# vulcan1.net
KiCad netlist of a schematic drawn in EAGLE
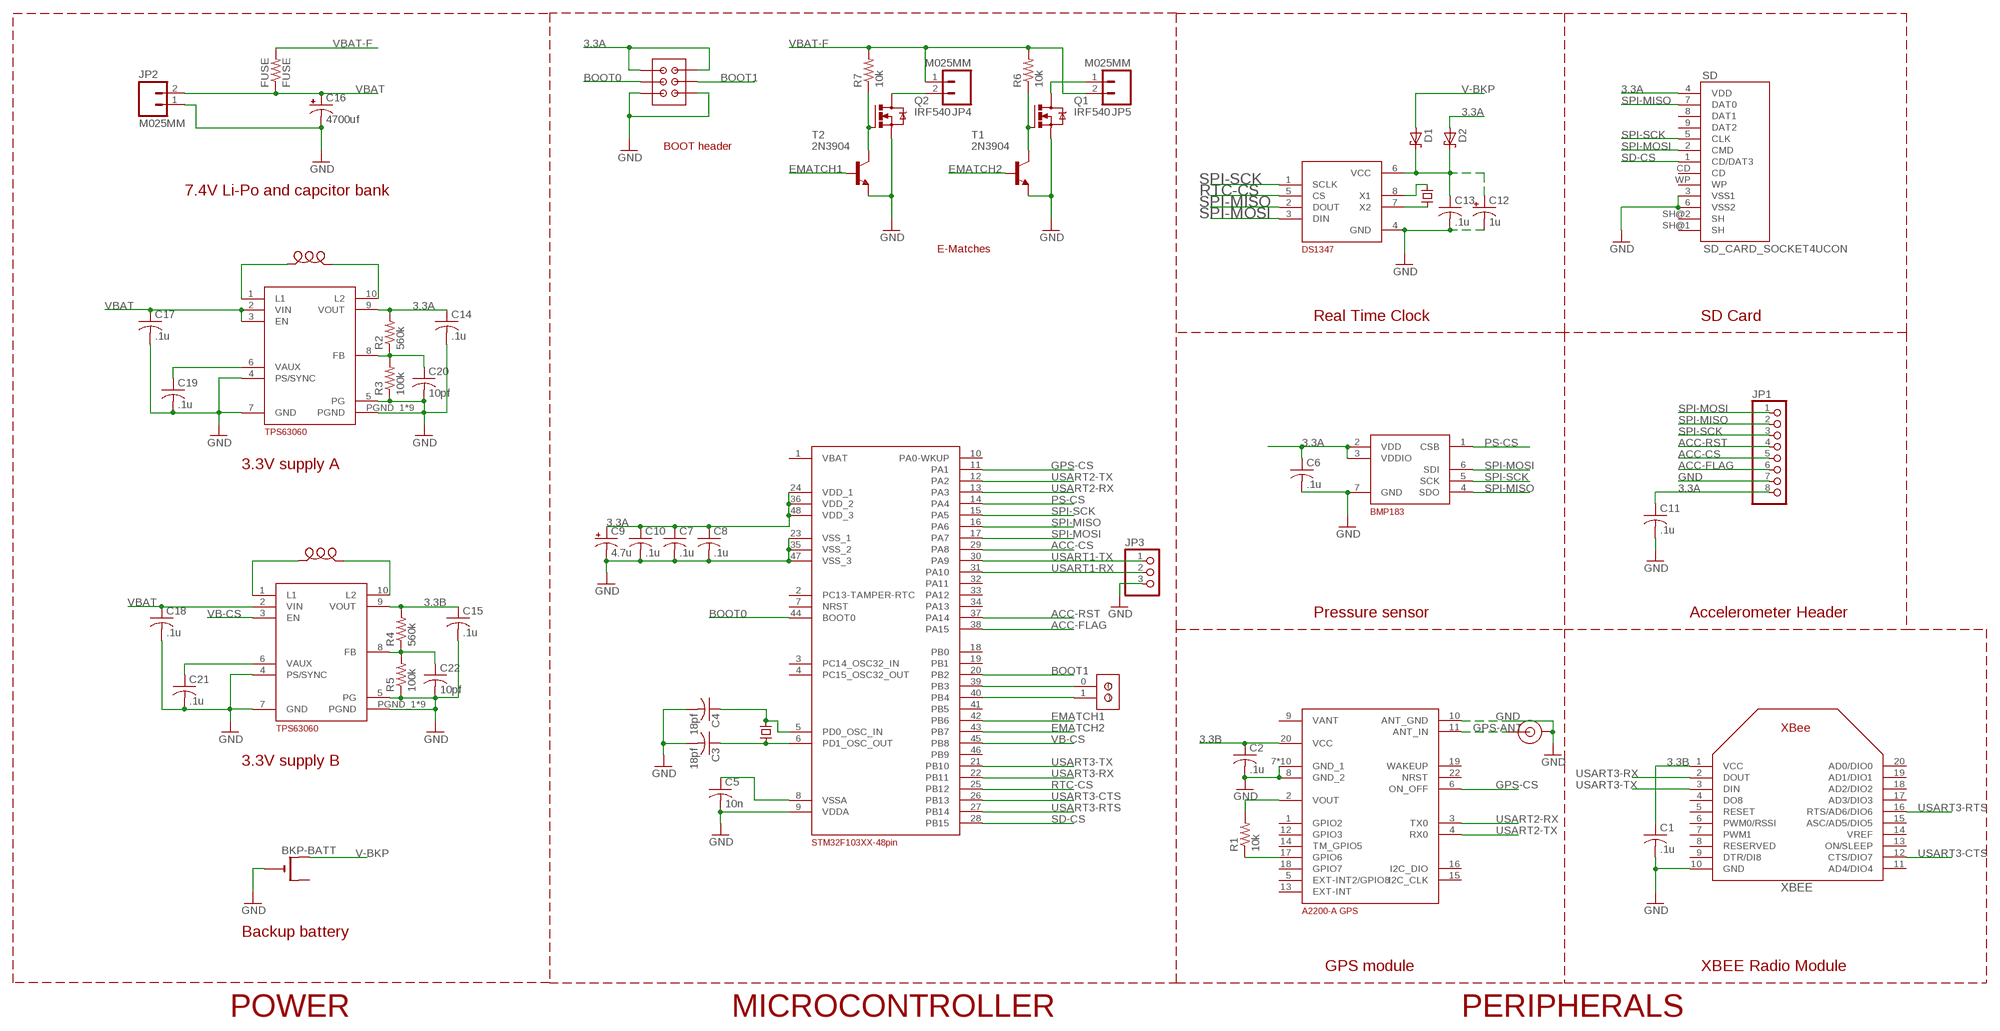
[diagram p0: schematic, sheet 1]

(export (version "E")
  (design (tool "Eeschema 10.0.6"))
  (components
    (comp (ref "A2200-A")
      (value "A2200-A")
      (footprint "eagle-import:GPS-MODULE")
      (libsource (lib "eagle-import") (part "A2200-A"))
    )
    (comp (ref "BKP-BATT")
      (value "CR1220THM")
      (footprint "eagle-import:CR1220-THM")
      (libsource (lib "eagle-import") (part "CR1220THM"))
    )
    (comp (ref "BMP1")
      (value "BMP183")
      (footprint "eagle-import:LGA-7")
      (libsource (lib "eagle-import") (part "BMP183"))
    )
    (comp (ref "C1")
      (value ".1u")
      (footprint "eagle-import:C025-030X050")
      (libsource (lib "eagle-import") (part "C-US025-030X050"))
    )
    (comp (ref "C2")
      (value ".1u")
      (footprint "eagle-import:C025-030X050")
      (libsource (lib "eagle-import") (part "C-US025-030X050"))
    )
    (comp (ref "C3")
      (value "18pf")
      (footprint "eagle-import:C025-030X050")
      (libsource (lib "eagle-import") (part "C-US025-030X050"))
    )
    (comp (ref "C4")
      (value "18pf")
      (footprint "eagle-import:C025-030X050")
      (libsource (lib "eagle-import") (part "C-US025-030X050"))
    )
    (comp (ref "C5")
      (value "10n")
      (footprint "eagle-import:C025-030X050")
      (libsource (lib "eagle-import") (part "C-US025-030X050"))
    )
    (comp (ref "C6")
      (value ".1u")
      (footprint "eagle-import:C025-030X050")
      (libsource (lib "eagle-import") (part "C-US025-030X050"))
    )
    (comp (ref "C7")
      (value ".1u")
      (footprint "eagle-import:C025-030X050")
      (libsource (lib "eagle-import") (part "C-US025-030X050"))
    )
    (comp (ref "C8")
      (value ".1u")
      (footprint "eagle-import:C025-030X050")
      (libsource (lib "eagle-import") (part "C-US025-030X050"))
    )
    (comp (ref "C9")
      (value "4.7u")
      (footprint "eagle-import:E2,5-6E")
      (libsource (lib "eagle-import") (part "CPOL-USE2,5-6E"))
    )
    (comp (ref "C10")
      (value ".1u")
      (footprint "eagle-import:C025-030X050")
      (libsource (lib "eagle-import") (part "C-US025-030X050"))
    )
    (comp (ref "C11")
      (value ".1u")
      (footprint "eagle-import:C025-030X050")
      (libsource (lib "eagle-import") (part "C-US025-030X050"))
    )
    (comp (ref "C12")
      (value "1u")
      (footprint "eagle-import:E2,5-6E")
      (libsource (lib "eagle-import") (part "CPOL-USE2,5-6E"))
    )
    (comp (ref "C13")
      (value ".1u")
      (footprint "eagle-import:C025-030X050")
      (libsource (lib "eagle-import") (part "C-US025-030X050"))
    )
    (comp (ref "C14")
      (value ".1u")
      (footprint "eagle-import:C025-030X050")
      (libsource (lib "eagle-import") (part "C-US025-030X050"))
    )
    (comp (ref "C15")
      (value ".1u")
      (footprint "eagle-import:C025-030X050")
      (libsource (lib "eagle-import") (part "C-US025-030X050"))
    )
    (comp (ref "C16")
      (value "4700uf")
      (footprint "eagle-import:E5-13")
      (libsource (lib "eagle-import") (part "CPOL-USE5-13"))
    )
    (comp (ref "C17")
      (value ".1u")
      (footprint "eagle-import:C025-030X050")
      (libsource (lib "eagle-import") (part "C-US025-030X050"))
    )
    (comp (ref "C18")
      (value ".1u")
      (footprint "eagle-import:C025-030X050")
      (libsource (lib "eagle-import") (part "C-US025-030X050"))
    )
    (comp (ref "C19")
      (value ".1u")
      (footprint "eagle-import:C025-030X050")
      (libsource (lib "eagle-import") (part "C-US025-030X050"))
    )
    (comp (ref "C20")
      (value "10pf")
      (footprint "eagle-import:C025-030X050")
      (libsource (lib "eagle-import") (part "C-US025-030X050"))
    )
    (comp (ref "C21")
      (value ".1u")
      (footprint "eagle-import:C025-030X050")
      (libsource (lib "eagle-import") (part "C-US025-030X050"))
    )
    (comp (ref "C22")
      (value "10pf")
      (footprint "eagle-import:C025-030X050")
      (libsource (lib "eagle-import") (part "C-US025-030X050"))
    )
    (comp (ref "D1")
      (value "SCHOTTKY-DIODEDO35-7")
      (footprint "eagle-import:DO35-7")
      (libsource (lib "eagle-import") (part "SCHOTTKY-DIODEDO35-7"))
    )
    (comp (ref "D2")
      (value "SCHOTTKY-DIODEDO35-7")
      (footprint "eagle-import:DO35-7")
      (libsource (lib "eagle-import") (part "SCHOTTKY-DIODEDO35-7"))
    )
    (comp (ref "DS1")
      (value "DS1347")
      (footprint "eagle-import:TDFN-T822-2")
      (libsource (lib "eagle-import") (part "DS1347"))
    )
    (comp (ref "FUSE")
      (value "FUSE")
      (footprint "eagle-import:0204_7")
      (libsource (lib "eagle-import") (part "R-US_0204/7"))
    )
    (comp (ref "JP1")
      (value "PINHD-1X8CLEANBIG")
      (footprint "eagle-import:1X08-CLEANBIG")
      (libsource (lib "eagle-import") (part "PINHD-1X8CLEANBIG"))
    )
    (comp (ref "JP2")
      (value "M025MM")
      (footprint "eagle-import:SCREWTERMINAL-5MM-2")
      (libsource (lib "eagle-import") (part "M025MM"))
    )
    (comp (ref "JP3")
      (value "PINHD-1X3CB")
      (footprint "eagle-import:1X03-CLEANBIG")
      (libsource (lib "eagle-import") (part "PINHD-1X3CB"))
    )
    (comp (ref "JP4")
      (value "M025MM")
      (footprint "eagle-import:SCREWTERMINAL-5MM-2")
      (libsource (lib "eagle-import") (part "M025MM"))
    )
    (comp (ref "JP5")
      (value "M025MM")
      (footprint "eagle-import:SCREWTERMINAL-5MM-2")
      (libsource (lib "eagle-import") (part "M025MM"))
    )
    (comp (ref "Q1")
      (value "IRF540")
      (footprint "eagle-import:TO220BV")
      (libsource (lib "eagle-import") (part "IRF540"))
    )
    (comp (ref "Q2")
      (value "IRF540")
      (footprint "eagle-import:TO220BV")
      (libsource (lib "eagle-import") (part "IRF540"))
    )
    (comp (ref "R1")
      (value "10k")
      (footprint "eagle-import:0204_7")
      (libsource (lib "eagle-import") (part "R-US_0204/7"))
    )
    (comp (ref "R2")
      (value "560k")
      (footprint "eagle-import:0204_7")
      (libsource (lib "eagle-import") (part "R-US_0204/7"))
    )
    (comp (ref "R3")
      (value "100k")
      (footprint "eagle-import:0204_7")
      (libsource (lib "eagle-import") (part "R-US_0204/7"))
    )
    (comp (ref "R4")
      (value "560k")
      (footprint "eagle-import:0204_7")
      (libsource (lib "eagle-import") (part "R-US_0204/7"))
    )
    (comp (ref "R5")
      (value "100k")
      (footprint "eagle-import:0204_7")
      (libsource (lib "eagle-import") (part "R-US_0204/7"))
    )
    (comp (ref "R6")
      (value "10k")
      (footprint "eagle-import:0204_7")
      (libsource (lib "eagle-import") (part "R-US_0204/7"))
    )
    (comp (ref "R7")
      (value "10k")
      (footprint "eagle-import:0204_7")
      (libsource (lib "eagle-import") (part "R-US_0204/7"))
    )
    (comp (ref "SD")
      (value "SD_CARD_SOCKET4UCON")
      (footprint "eagle-import:SDCARD_4UCONN")
      (libsource (lib "eagle-import") (part "SD_CARD_SOCKET4UCON"))
    )
    (comp (ref "T1")
      (value "2N3904")
      (footprint "eagle-import:TO92")
      (libsource (lib "eagle-import") (part "2N3904"))
    )
    (comp (ref "T2")
      (value "2N3904")
      (footprint "eagle-import:TO92")
      (libsource (lib "eagle-import") (part "2N3904"))
    )
    (comp (ref "TPS63060-A")
      (value "TPS63060")
      (footprint "eagle-import:PWSON-N10")
      (libsource (lib "eagle-import") (part "TPS63060"))
    )
    (comp (ref "TPS63060-B")
      (value "TPS63060")
      (footprint "eagle-import:PWSON-N10")
      (libsource (lib "eagle-import") (part "TPS63060"))
    )
    (comp (ref "U$1")
      (value "SMA")
      (footprint "eagle-import:SMA")
      (libsource (lib "eagle-import") (part "SMA"))
    )
    (comp (ref "U$2")
      (value "HC/49US(AT49)")
      (footprint "eagle-import:HC_49US")
      (libsource (lib "eagle-import") (part "HC/49US(AT49)"))
    )
    (comp (ref "U$3")
      (value "STM32F103XX-48PIN")
      (footprint "eagle-import:LQFP48")
      (libsource (lib "eagle-import") (part "STM32F103XX-48PIN"))
    )
    (comp (ref "U$4")
      (value "ECX-306X")
      (footprint "eagle-import:ECX-306X")
      (libsource (lib "eagle-import") (part "ECX-306X"))
    )
    (comp (ref "U$5")
      (value "ASPI-0520LR")
      (footprint "eagle-import:L-0520LR")
      (libsource (lib "eagle-import") (part "ASPI-0520LR"))
    )
    (comp (ref "U$6")
      (value "ASPI-0520LR")
      (footprint "eagle-import:L-0520LR")
      (libsource (lib "eagle-import") (part "ASPI-0520LR"))
    )
    (comp (ref "U$7")
      (value "2X3")
      (footprint "eagle-import:2X3")
      (libsource (lib "eagle-import") (part "2X3"))
    )
    (comp (ref "U$8")
      (value "1X2HEADER")
      (footprint "eagle-import:1X2HEADER")
      (libsource (lib "eagle-import") (part "1X2HEADER"))
    )
    (comp (ref "XBEE")
      (value "XBEE")
      (footprint "eagle-import:XBEE")
      (libsource (lib "eagle-import") (part "XBEE"))
    )
  )
  (nets
    (net (code "1") (name "/3.3A") (class "Default")
      (node (ref "BMP1") (pin "2") (pinfunction "VDD_2") (pintype "bidirectional"))
      (node (ref "BMP1") (pin "3") (pinfunction "VDDIO_3") (pintype "bidirectional"))
      (node (ref "C10") (pin "1") (pinfunction "1_1") (pintype "passive"))
      (node (ref "C11") (pin "1") (pinfunction "1_1") (pintype "passive"))
      (node (ref "C14") (pin "1") (pinfunction "1_1") (pintype "passive"))
      (node (ref "C6") (pin "1") (pinfunction "1_1") (pintype "passive"))
      (node (ref "C7") (pin "1") (pinfunction "1_1") (pintype "passive"))
      (node (ref "C8") (pin "1") (pinfunction "1_1") (pintype "passive"))
      (node (ref "C9") (pin "+") (pinfunction "+_+") (pintype "passive"))
      (node (ref "D2") (pin "A") (pinfunction "A_A") (pintype "passive"))
      (node (ref "JP1") (pin "8") (pinfunction "8_8") (pintype "passive"))
      (node (ref "R2") (pin "2") (pinfunction "2_2") (pintype "passive"))
      (node (ref "SD") (pin "4") (pinfunction "VDD_4") (pintype "power_in"))
      (node (ref "TPS63060-A") (pin "9") (pinfunction "VOUT_9") (pintype "bidirectional"))
      (node (ref "U$3") (pin "24") (pinfunction "VDD_1_24") (pintype "bidirectional"))
      (node (ref "U$3") (pin "36") (pinfunction "VDD_2_36") (pintype "bidirectional"))
      (node (ref "U$3") (pin "48") (pinfunction "VDD_3_48") (pintype "bidirectional"))
      (node (ref "U$7") (pin "1") (pinfunction "1_1") (pintype "bidirectional"))
      (node (ref "U$7") (pin "2") (pinfunction "2_2") (pintype "bidirectional"))
    )
    (net (code "2") (name "/3.3B") (class "Default")
      (node (ref "A2200-A") (pin "20") (pinfunction "VCC_20") (pintype "bidirectional"))
      (node (ref "C1") (pin "1") (pinfunction "1_1") (pintype "passive"))
      (node (ref "C15") (pin "1") (pinfunction "1_1") (pintype "passive"))
      (node (ref "C2") (pin "1") (pinfunction "1_1") (pintype "passive"))
      (node (ref "R4") (pin "2") (pinfunction "2_2") (pintype "passive"))
      (node (ref "TPS63060-B") (pin "9") (pinfunction "VOUT_9") (pintype "bidirectional"))
      (node (ref "XBEE") (pin "1") (pinfunction "VCC_1") (pintype "power_in"))
    )
    (net (code "3") (name "/ACC-CS") (class "Default")
      (node (ref "JP1") (pin "5") (pinfunction "5_5") (pintype "passive"))
      (node (ref "U$3") (pin "29") (pinfunction "PA8_29") (pintype "bidirectional"))
    )
    (net (code "4") (name "/ACC-FLAG") (class "Default")
      (node (ref "JP1") (pin "6") (pinfunction "6_6") (pintype "passive"))
      (node (ref "U$3") (pin "38") (pinfunction "PA15_38") (pintype "bidirectional"))
    )
    (net (code "5") (name "/ACC-RST") (class "Default")
      (node (ref "JP1") (pin "4") (pinfunction "4_4") (pintype "passive"))
      (node (ref "U$3") (pin "37") (pinfunction "PA14_37") (pintype "bidirectional"))
    )
    (net (code "6") (name "/BOOT0") (class "Default")
      (node (ref "U$3") (pin "44") (pinfunction "BOOT0_44") (pintype "bidirectional"))
      (node (ref "U$7") (pin "3") (pinfunction "3_3") (pintype "bidirectional"))
    )
    (net (code "7") (name "/BOOT1") (class "Default")
      (node (ref "U$3") (pin "20") (pinfunction "PB2_20") (pintype "bidirectional"))
      (node (ref "U$7") (pin "4") (pinfunction "4_4") (pintype "bidirectional"))
    )
    (net (code "8") (name "/EMATCH1") (class "Default")
      (node (ref "T2") (pin "2") (pinfunction "B_2") (pintype "passive"))
      (node (ref "U$3") (pin "42") (pinfunction "PB6_42") (pintype "bidirectional"))
    )
    (net (code "9") (name "/EMATCH2") (class "Default")
      (node (ref "T1") (pin "2") (pinfunction "B_2") (pintype "passive"))
      (node (ref "U$3") (pin "43") (pinfunction "PB7_43") (pintype "bidirectional"))
    )
    (net (code "10") (name "/GPS-ANT") (class "Default")
      (node (ref "A2200-A") (pin "11") (pinfunction "ANT_IN_11") (pintype "bidirectional"))
      (node (ref "U$1") (pin "3") (pinfunction "IN_3") (pintype "bidirectional"))
    )
    (net (code "11") (name "/GPS-CS") (class "Default")
      (node (ref "A2200-A") (pin "6") (pinfunction "ON_OFF_6") (pintype "bidirectional"))
      (node (ref "U$3") (pin "11") (pinfunction "PA1_11") (pintype "bidirectional"))
    )
    (net (code "12") (name "/PS-CS") (class "Default")
      (node (ref "BMP1") (pin "1") (pinfunction "CSB_1") (pintype "bidirectional"))
      (node (ref "U$3") (pin "14") (pinfunction "PA4_14") (pintype "bidirectional"))
    )
    (net (code "13") (name "/RTC-CS") (class "Default")
      (node (ref "DS1") (pin "5") (pinfunction "CS_5") (pintype "bidirectional"))
      (node (ref "U$3") (pin "25") (pinfunction "PB12_25") (pintype "bidirectional"))
    )
    (net (code "14") (name "/SD-CS") (class "Default")
      (node (ref "SD") (pin "1") (pinfunction "CD/DAT3_1") (pintype "bidirectional"))
      (node (ref "U$3") (pin "28") (pinfunction "PB15_28") (pintype "bidirectional"))
    )
    (net (code "15") (name "/SPI-MISO") (class "Default")
      (node (ref "BMP1") (pin "4") (pinfunction "SDO_4") (pintype "bidirectional"))
      (node (ref "DS1") (pin "2") (pinfunction "DOUT_2") (pintype "bidirectional"))
      (node (ref "JP1") (pin "2") (pinfunction "2_2") (pintype "passive"))
      (node (ref "SD") (pin "7") (pinfunction "DAT0_7") (pintype "bidirectional"))
      (node (ref "U$3") (pin "16") (pinfunction "PA6_16") (pintype "bidirectional"))
    )
    (net (code "16") (name "/SPI-MOSI") (class "Default")
      (node (ref "BMP1") (pin "6") (pinfunction "SDI_6") (pintype "bidirectional"))
      (node (ref "DS1") (pin "3") (pinfunction "DIN_3") (pintype "bidirectional"))
      (node (ref "JP1") (pin "1") (pinfunction "1_1") (pintype "passive"))
      (node (ref "SD") (pin "2") (pinfunction "CMD_2") (pintype "bidirectional"))
      (node (ref "U$3") (pin "17") (pinfunction "PA7_17") (pintype "bidirectional"))
    )
    (net (code "17") (name "/SPI-SCK") (class "Default")
      (node (ref "BMP1") (pin "5") (pinfunction "SCK_5") (pintype "bidirectional"))
      (node (ref "DS1") (pin "1") (pinfunction "SCLK_1") (pintype "bidirectional"))
      (node (ref "JP1") (pin "3") (pinfunction "3_3") (pintype "passive"))
      (node (ref "SD") (pin "5") (pinfunction "CLK_5") (pintype "bidirectional"))
      (node (ref "U$3") (pin "15") (pinfunction "PA5_15") (pintype "bidirectional"))
    )
    (net (code "18") (name "/USART1-RX") (class "Default")
      (node (ref "JP3") (pin "2") (pinfunction "2_2") (pintype "passive"))
      (node (ref "U$3") (pin "31") (pinfunction "PA10_31") (pintype "bidirectional"))
    )
    (net (code "19") (name "/USART1-TX") (class "Default")
      (node (ref "JP3") (pin "1") (pinfunction "1_1") (pintype "passive"))
      (node (ref "U$3") (pin "30") (pinfunction "PA9_30") (pintype "bidirectional"))
    )
    (net (code "20") (name "/USART2-RX") (class "Default")
      (node (ref "A2200-A") (pin "3") (pinfunction "TX0_3") (pintype "bidirectional"))
      (node (ref "U$3") (pin "13") (pinfunction "PA3_13") (pintype "bidirectional"))
    )
    (net (code "21") (name "/USART2-TX") (class "Default")
      (node (ref "A2200-A") (pin "4") (pinfunction "RX0_4") (pintype "bidirectional"))
      (node (ref "U$3") (pin "12") (pinfunction "PA2_12") (pintype "bidirectional"))
    )
    (net (code "22") (name "/USART3-CTS") (class "Default")
      (node (ref "U$3") (pin "26") (pinfunction "PB13_26") (pintype "bidirectional"))
      (node (ref "XBEE") (pin "12") (pinfunction "CTS/DIO7_12") (pintype "bidirectional"))
    )
    (net (code "23") (name "/USART3-RTS") (class "Default")
      (node (ref "U$3") (pin "27") (pinfunction "PB14_27") (pintype "bidirectional"))
      (node (ref "XBEE") (pin "16") (pinfunction "RTS/AD6/DIO6_16") (pintype "bidirectional"))
    )
    (net (code "24") (name "/USART3-RX") (class "Default")
      (node (ref "U$3") (pin "22") (pinfunction "PB11_22") (pintype "bidirectional"))
      (node (ref "XBEE") (pin "2") (pinfunction "DOUT_2") (pintype "output"))
    )
    (net (code "25") (name "/USART3-TX") (class "Default")
      (node (ref "U$3") (pin "21") (pinfunction "PB10_21") (pintype "bidirectional"))
      (node (ref "XBEE") (pin "3") (pinfunction "DIN_3") (pintype "input"))
    )
    (net (code "26") (name "/V-BKP") (class "Default")
      (node (ref "BKP-BATT") (pin "+1") (pinfunction "+_+1") (pintype "passive"))
      (node (ref "D1") (pin "A") (pinfunction "A_A") (pintype "passive"))
    )
    (net (code "27") (name "/VB-CS") (class "Default")
      (node (ref "TPS63060-B") (pin "3") (pinfunction "EN_3") (pintype "bidirectional"))
      (node (ref "U$3") (pin "45") (pinfunction "PB8_45") (pintype "bidirectional"))
    )
    (net (code "28") (name "/VBAT") (class "Default")
      (node (ref "C16") (pin "+") (pinfunction "+_+") (pintype "passive"))
      (node (ref "C17") (pin "1") (pinfunction "1_1") (pintype "passive"))
      (node (ref "C18") (pin "1") (pinfunction "1_1") (pintype "passive"))
      (node (ref "FUSE") (pin "1") (pinfunction "1_1") (pintype "passive"))
      (node (ref "JP2") (pin "2") (pinfunction "2_2") (pintype "passive"))
      (node (ref "TPS63060-A") (pin "2") (pinfunction "VIN_2") (pintype "bidirectional"))
      (node (ref "TPS63060-A") (pin "3") (pinfunction "EN_3") (pintype "bidirectional"))
      (node (ref "TPS63060-B") (pin "2") (pinfunction "VIN_2") (pintype "bidirectional"))
    )
    (net (code "29") (name "/VBAT-F") (class "Default")
      (node (ref "FUSE") (pin "2") (pinfunction "2_2") (pintype "passive"))
      (node (ref "JP4") (pin "1") (pinfunction "1_1") (pintype "passive"))
      (node (ref "JP5") (pin "2") (pinfunction "2_2") (pintype "passive"))
      (node (ref "R6") (pin "2") (pinfunction "2_2") (pintype "passive"))
      (node (ref "R7") (pin "2") (pinfunction "2_2") (pintype "passive"))
    )
    (net (code "30") (name "GND") (class "Default")
      (node (ref "A2200-A") (pin "10") (pinfunction "ANT_GND_10") (pintype "bidirectional"))
      (node (ref "A2200-A") (pin "7") (pinfunction "GND_1_7") (pintype "bidirectional"))
      (node (ref "A2200-A") (pin "8") (pinfunction "GND_2_8") (pintype "bidirectional"))
      (node (ref "A2200-A") (pin "P$1") (pinfunction "GND_1_P$1") (pintype "bidirectional"))
      (node (ref "A2200-A") (pin "P$2") (pinfunction "GND_1_P$2") (pintype "bidirectional"))
      (node (ref "A2200-A") (pin "P$3") (pinfunction "GND_1_P$3") (pintype "bidirectional"))
      (node (ref "A2200-A") (pin "P$4") (pinfunction "GND_1_P$4") (pintype "bidirectional"))
      (node (ref "A2200-A") (pin "P$5") (pinfunction "GND_1_P$5") (pintype "bidirectional"))
      (node (ref "A2200-A") (pin "P$6") (pinfunction "GND_1_P$6") (pintype "bidirectional"))
      (node (ref "A2200-A") (pin "P$7") (pinfunction "GND_1_P$7") (pintype "bidirectional"))
      (node (ref "A2200-A") (pin "P$8") (pinfunction "GND_1_P$8") (pintype "bidirectional"))
      (node (ref "A2200-A") (pin "P$9") (pinfunction "GND_1_P$9") (pintype "bidirectional"))
      (node (ref "BKP-BATT") (pin "-") (pinfunction "-_-") (pintype "passive"))
      (node (ref "BMP1") (pin "7") (pinfunction "GND_7") (pintype "bidirectional"))
      (node (ref "C1") (pin "2") (pinfunction "2_2") (pintype "passive"))
      (node (ref "C10") (pin "2") (pinfunction "2_2") (pintype "passive"))
      (node (ref "C11") (pin "2") (pinfunction "2_2") (pintype "passive"))
      (node (ref "C12") (pin "-") (pinfunction "-_-") (pintype "passive"))
      (node (ref "C13") (pin "2") (pinfunction "2_2") (pintype "passive"))
      (node (ref "C14") (pin "2") (pinfunction "2_2") (pintype "passive"))
      (node (ref "C15") (pin "2") (pinfunction "2_2") (pintype "passive"))
      (node (ref "C16") (pin "-") (pinfunction "-_-") (pintype "passive"))
      (node (ref "C17") (pin "2") (pinfunction "2_2") (pintype "passive"))
      (node (ref "C18") (pin "2") (pinfunction "2_2") (pintype "passive"))
      (node (ref "C19") (pin "2") (pinfunction "2_2") (pintype "passive"))
      (node (ref "C2") (pin "2") (pinfunction "2_2") (pintype "passive"))
      (node (ref "C20") (pin "2") (pinfunction "2_2") (pintype "passive"))
      (node (ref "C21") (pin "2") (pinfunction "2_2") (pintype "passive"))
      (node (ref "C22") (pin "2") (pinfunction "2_2") (pintype "passive"))
      (node (ref "C3") (pin "2") (pinfunction "2_2") (pintype "passive"))
      (node (ref "C4") (pin "2") (pinfunction "2_2") (pintype "passive"))
      (node (ref "C5") (pin "2") (pinfunction "2_2") (pintype "passive"))
      (node (ref "C6") (pin "2") (pinfunction "2_2") (pintype "passive"))
      (node (ref "C7") (pin "2") (pinfunction "2_2") (pintype "passive"))
      (node (ref "C8") (pin "2") (pinfunction "2_2") (pintype "passive"))
      (node (ref "C9") (pin "-") (pinfunction "-_-") (pintype "passive"))
      (node (ref "DS1") (pin "4") (pinfunction "GND_4") (pintype "bidirectional"))
      (node (ref "JP1") (pin "7") (pinfunction "7_7") (pintype "passive"))
      (node (ref "JP2") (pin "1") (pinfunction "1_1") (pintype "passive"))
      (node (ref "JP3") (pin "3") (pinfunction "3_3") (pintype "passive"))
      (node (ref "Q1") (pin "S") (pinfunction "S_S") (pintype "passive"))
      (node (ref "Q2") (pin "S") (pinfunction "S_S") (pintype "passive"))
      (node (ref "R3") (pin "1") (pinfunction "1_1") (pintype "passive"))
      (node (ref "R5") (pin "1") (pinfunction "1_1") (pintype "passive"))
      (node (ref "SD") (pin "3") (pinfunction "VSS1_3") (pintype "power_in"))
      (node (ref "SD") (pin "6") (pinfunction "VSS2_6") (pintype "power_in"))
      (node (ref "T1") (pin "3") (pinfunction "E_3") (pintype "passive"))
      (node (ref "T2") (pin "3") (pinfunction "E_3") (pintype "passive"))
      (node (ref "TPS63060-A") (pin "4") (pinfunction "PS/SYNC_4") (pintype "bidirectional"))
      (node (ref "TPS63060-A") (pin "5") (pinfunction "PG_5") (pintype "bidirectional"))
      (node (ref "TPS63060-A") (pin "7") (pinfunction "GND_7") (pintype "bidirectional"))
      (node (ref "TPS63060-A") (pin "PGND_1") (pinfunction "PGND_PGND_1") (pintype "bidirectional"))
      (node (ref "TPS63060-A") (pin "PGND_2") (pinfunction "PGND_PGND_2") (pintype "bidirectional"))
      (node (ref "TPS63060-A") (pin "PGND_3") (pinfunction "PGND_PGND_3") (pintype "bidirectional"))
      (node (ref "TPS63060-A") (pin "PGND_4") (pinfunction "PGND_PGND_4") (pintype "bidirectional"))
      (node (ref "TPS63060-A") (pin "PGND_5") (pinfunction "PGND_PGND_5") (pintype "bidirectional"))
      (node (ref "TPS63060-A") (pin "PGND_6") (pinfunction "PGND_PGND_6") (pintype "bidirectional"))
      (node (ref "TPS63060-A") (pin "PGND_7") (pinfunction "PGND_PGND_7") (pintype "bidirectional"))
      (node (ref "TPS63060-A") (pin "PGND_8") (pinfunction "PGND_PGND_8") (pintype "bidirectional"))
      (node (ref "TPS63060-A") (pin "PGND_9") (pinfunction "PGND_PGND_9") (pintype "bidirectional"))
      (node (ref "TPS63060-B") (pin "4") (pinfunction "PS/SYNC_4") (pintype "bidirectional"))
      (node (ref "TPS63060-B") (pin "5") (pinfunction "PG_5") (pintype "bidirectional"))
      (node (ref "TPS63060-B") (pin "7") (pinfunction "GND_7") (pintype "bidirectional"))
      (node (ref "TPS63060-B") (pin "PGND_1") (pinfunction "PGND_PGND_1") (pintype "bidirectional"))
      (node (ref "TPS63060-B") (pin "PGND_2") (pinfunction "PGND_PGND_2") (pintype "bidirectional"))
      (node (ref "TPS63060-B") (pin "PGND_3") (pinfunction "PGND_PGND_3") (pintype "bidirectional"))
      (node (ref "TPS63060-B") (pin "PGND_4") (pinfunction "PGND_PGND_4") (pintype "bidirectional"))
      (node (ref "TPS63060-B") (pin "PGND_5") (pinfunction "PGND_PGND_5") (pintype "bidirectional"))
      (node (ref "TPS63060-B") (pin "PGND_6") (pinfunction "PGND_PGND_6") (pintype "bidirectional"))
      (node (ref "TPS63060-B") (pin "PGND_7") (pinfunction "PGND_PGND_7") (pintype "bidirectional"))
      (node (ref "TPS63060-B") (pin "PGND_8") (pinfunction "PGND_PGND_8") (pintype "bidirectional"))
      (node (ref "TPS63060-B") (pin "PGND_9") (pinfunction "PGND_PGND_9") (pintype "bidirectional"))
      (node (ref "U$1") (pin "1") (pinfunction "OUT_1") (pintype "bidirectional"))
      (node (ref "U$1") (pin "2") (pinfunction "OUT_2") (pintype "bidirectional"))
      (node (ref "U$3") (pin "23") (pinfunction "VSS_1_23") (pintype "bidirectional"))
      (node (ref "U$3") (pin "35") (pinfunction "VSS_2_35") (pintype "bidirectional"))
      (node (ref "U$3") (pin "47") (pinfunction "VSS_3_47") (pintype "bidirectional"))
      (node (ref "U$3") (pin "9") (pinfunction "VDDA_9") (pintype "bidirectional"))
      (node (ref "U$7") (pin "5") (pinfunction "5_5") (pintype "bidirectional"))
      (node (ref "U$7") (pin "6") (pinfunction "6_6") (pintype "bidirectional"))
      (node (ref "XBEE") (pin "10") (pinfunction "GND_10") (pintype "power_in"))
    )
    (net (code "31") (name "Net-(A2200-A-GPIO6)") (class "Default")
      (node (ref "A2200-A") (pin "17") (pinfunction "GPIO6_17") (pintype "bidirectional"))
      (node (ref "R1") (pin "1") (pinfunction "1_1") (pintype "passive"))
    )
    (net (code "32") (name "Net-(A2200-A-VOUT)") (class "Default")
      (node (ref "A2200-A") (pin "2") (pinfunction "VOUT_2") (pintype "bidirectional"))
      (node (ref "R1") (pin "2") (pinfunction "2_2") (pintype "passive"))
    )
    (net (code "33") (name "Net-(DS1-VCC)") (class "Default")
      (node (ref "C12") (pin "+") (pinfunction "+_+") (pintype "passive"))
      (node (ref "C13") (pin "1") (pinfunction "1_1") (pintype "passive"))
      (node (ref "D1") (pin "C") (pinfunction "C_C") (pintype "passive"))
      (node (ref "D2") (pin "C") (pinfunction "C_C") (pintype "passive"))
      (node (ref "DS1") (pin "6") (pinfunction "VCC_6") (pintype "bidirectional"))
    )
    (net (code "34") (name "Net-(DS1-X1)") (class "Default")
      (node (ref "DS1") (pin "8") (pinfunction "X1_8") (pintype "bidirectional"))
      (node (ref "U$4") (pin "4") (pinfunction "P$2_4") (pintype "bidirectional"))
    )
    (net (code "35") (name "Net-(DS1-X2)") (class "Default")
      (node (ref "DS1") (pin "7") (pinfunction "X2_7") (pintype "bidirectional"))
      (node (ref "U$4") (pin "1") (pinfunction "P$1_1") (pintype "bidirectional"))
    )
    (net (code "36") (name "Net-(JP4-Pad2)") (class "Default")
      (node (ref "JP4") (pin "2") (pinfunction "2_2") (pintype "passive"))
      (node (ref "Q2") (pin "D") (pinfunction "D_D") (pintype "passive"))
    )
    (net (code "37") (name "Net-(JP5-Pad1)") (class "Default")
      (node (ref "JP5") (pin "1") (pinfunction "1_1") (pintype "passive"))
      (node (ref "Q1") (pin "D") (pinfunction "D_D") (pintype "passive"))
    )
    (net (code "38") (name "Net-(T1-C)") (class "Default")
      (node (ref "Q1") (pin "G") (pinfunction "G_G") (pintype "passive"))
      (node (ref "R6") (pin "1") (pinfunction "1_1") (pintype "passive"))
      (node (ref "T1") (pin "1") (pinfunction "C_1") (pintype "passive"))
    )
    (net (code "39") (name "Net-(T2-C)") (class "Default")
      (node (ref "Q2") (pin "G") (pinfunction "G_G") (pintype "passive"))
      (node (ref "R7") (pin "1") (pinfunction "1_1") (pintype "passive"))
      (node (ref "T2") (pin "1") (pinfunction "C_1") (pintype "passive"))
    )
    (net (code "40") (name "Net-(TPS63060-A-FB)") (class "Default")
      (node (ref "C20") (pin "1") (pinfunction "1_1") (pintype "passive"))
      (node (ref "R2") (pin "1") (pinfunction "1_1") (pintype "passive"))
      (node (ref "R3") (pin "2") (pinfunction "2_2") (pintype "passive"))
      (node (ref "TPS63060-A") (pin "8") (pinfunction "FB_8") (pintype "bidirectional"))
    )
    (net (code "41") (name "Net-(TPS63060-A-L1)") (class "Default")
      (node (ref "TPS63060-A") (pin "1") (pinfunction "L1_1") (pintype "bidirectional"))
      (node (ref "U$5") (pin "P$1") (pinfunction "P$1_P$1") (pintype "bidirectional"))
    )
    (net (code "42") (name "Net-(TPS63060-A-L2)") (class "Default")
      (node (ref "TPS63060-A") (pin "10") (pinfunction "L2_10") (pintype "bidirectional"))
      (node (ref "U$5") (pin "P$2") (pinfunction "P$2_P$2") (pintype "bidirectional"))
    )
    (net (code "43") (name "Net-(TPS63060-A-VAUX)") (class "Default")
      (node (ref "C19") (pin "1") (pinfunction "1_1") (pintype "passive"))
      (node (ref "TPS63060-A") (pin "6") (pinfunction "VAUX_6") (pintype "bidirectional"))
    )
    (net (code "44") (name "Net-(TPS63060-B-FB)") (class "Default")
      (node (ref "C22") (pin "1") (pinfunction "1_1") (pintype "passive"))
      (node (ref "R4") (pin "1") (pinfunction "1_1") (pintype "passive"))
      (node (ref "R5") (pin "2") (pinfunction "2_2") (pintype "passive"))
      (node (ref "TPS63060-B") (pin "8") (pinfunction "FB_8") (pintype "bidirectional"))
    )
    (net (code "45") (name "Net-(TPS63060-B-L1)") (class "Default")
      (node (ref "TPS63060-B") (pin "1") (pinfunction "L1_1") (pintype "bidirectional"))
      (node (ref "U$6") (pin "P$1") (pinfunction "P$1_P$1") (pintype "bidirectional"))
    )
    (net (code "46") (name "Net-(TPS63060-B-L2)") (class "Default")
      (node (ref "TPS63060-B") (pin "10") (pinfunction "L2_10") (pintype "bidirectional"))
      (node (ref "U$6") (pin "P$2") (pinfunction "P$2_P$2") (pintype "bidirectional"))
    )
    (net (code "47") (name "Net-(TPS63060-B-VAUX)") (class "Default")
      (node (ref "C21") (pin "1") (pinfunction "1_1") (pintype "passive"))
      (node (ref "TPS63060-B") (pin "6") (pinfunction "VAUX_6") (pintype "bidirectional"))
    )
    (net (code "48") (name "Net-(U$2-P$1)") (class "Default")
      (node (ref "C3") (pin "1") (pinfunction "1_1") (pintype "passive"))
      (node (ref "U$2") (pin "1") (pinfunction "P$1_1") (pintype "bidirectional"))
      (node (ref "U$3") (pin "6") (pinfunction "PD1_OSC_OUT_6") (pintype "bidirectional"))
    )
    (net (code "49") (name "Net-(U$2-P$2)") (class "Default")
      (node (ref "C4") (pin "1") (pinfunction "1_1") (pintype "passive"))
      (node (ref "U$2") (pin "2") (pinfunction "P$2_2") (pintype "bidirectional"))
      (node (ref "U$3") (pin "5") (pinfunction "PD0_OSC_IN_5") (pintype "bidirectional"))
    )
    (net (code "50") (name "Net-(U$3-PB3)") (class "Default")
      (node (ref "U$3") (pin "39") (pinfunction "PB3_39") (pintype "bidirectional"))
      (node (ref "U$8") (pin "0") (pinfunction "0_0") (pintype "bidirectional"))
    )
    (net (code "51") (name "Net-(U$3-PB4)") (class "Default")
      (node (ref "U$3") (pin "40") (pinfunction "PB4_40") (pintype "bidirectional"))
      (node (ref "U$8") (pin "1") (pinfunction "1_1") (pintype "bidirectional"))
    )
    (net (code "52") (name "Net-(U$3-VSSA)") (class "Default")
      (node (ref "C5") (pin "1") (pinfunction "1_1") (pintype "passive"))
      (node (ref "U$3") (pin "8") (pinfunction "VSSA_8") (pintype "bidirectional"))
    )
    (net (code "53") (name "unconnected-(A2200-A-EXT-INT-Pad13)") (class "Default")
      (node (ref "A2200-A") (pin "13") (pinfunction "EXT-INT_13") (pintype "bidirectional"))
    )
    (net (code "54") (name "unconnected-(A2200-A-EXT-INT2{slash}GPIO8-Pad5)") (class "Default")
      (node (ref "A2200-A") (pin "5") (pinfunction "EXT-INT2/GPIO8_5") (pintype "bidirectional"))
    )
    (net (code "55") (name "unconnected-(A2200-A-GPIO2-Pad1)") (class "Default")
      (node (ref "A2200-A") (pin "1") (pinfunction "GPIO2_1") (pintype "bidirectional"))
    )
    (net (code "56") (name "unconnected-(A2200-A-GPIO3-Pad12)") (class "Default")
      (node (ref "A2200-A") (pin "12") (pinfunction "GPIO3_12") (pintype "bidirectional"))
    )
    (net (code "57") (name "unconnected-(A2200-A-GPIO7-Pad18)") (class "Default")
      (node (ref "A2200-A") (pin "18") (pinfunction "GPIO7_18") (pintype "bidirectional"))
    )
    (net (code "58") (name "unconnected-(A2200-A-I2C_CLK-Pad15)") (class "Default")
      (node (ref "A2200-A") (pin "15") (pinfunction "I2C_CLK_15") (pintype "bidirectional"))
    )
    (net (code "59") (name "unconnected-(A2200-A-I2C_DIO-Pad16)") (class "Default")
      (node (ref "A2200-A") (pin "16") (pinfunction "I2C_DIO_16") (pintype "bidirectional"))
    )
    (net (code "60") (name "unconnected-(A2200-A-NRST-Pad22)") (class "Default")
      (node (ref "A2200-A") (pin "22") (pinfunction "NRST_22") (pintype "bidirectional"))
    )
    (net (code "61") (name "unconnected-(A2200-A-TM_GPIO5-Pad14)") (class "Default")
      (node (ref "A2200-A") (pin "14") (pinfunction "TM_GPIO5_14") (pintype "bidirectional"))
    )
    (net (code "62") (name "unconnected-(A2200-A-VANT-Pad9)") (class "Default")
      (node (ref "A2200-A") (pin "9") (pinfunction "VANT_9") (pintype "bidirectional"))
    )
    (net (code "63") (name "unconnected-(A2200-A-WAKEUP-Pad19)") (class "Default")
      (node (ref "A2200-A") (pin "19") (pinfunction "WAKEUP_19") (pintype "bidirectional"))
    )
    (net (code "64") (name "unconnected-(BKP-BATT-+1-Pad+2)") (class "Default")
      (node (ref "BKP-BATT") (pin "+2") (pinfunction "+1_+2") (pintype "passive"))
    )
    (net (code "65") (name "unconnected-(SD-DAT1-Pad8)") (class "Default")
      (node (ref "SD") (pin "8") (pinfunction "DAT1_8") (pintype "bidirectional"))
    )
    (net (code "66") (name "unconnected-(SD-DAT2-Pad9)") (class "Default")
      (node (ref "SD") (pin "9") (pinfunction "DAT2_9") (pintype "bidirectional"))
    )
    (net (code "67") (name "unconnected-(SD-PadCD)") (class "Default")
      (node (ref "SD") (pin "CD") (pinfunction "CD_CD") (pintype "bidirectional"))
    )
    (net (code "68") (name "unconnected-(SD-PadWP)") (class "Default")
      (node (ref "SD") (pin "WP") (pinfunction "WP_WP") (pintype "bidirectional"))
    )
    (net (code "69") (name "unconnected-(SD-SH-PadSH@1)") (class "Default")
      (node (ref "SD") (pin "SH@1") (pinfunction "SH_SH@1") (pintype "bidirectional"))
    )
    (net (code "70") (name "unconnected-(SD-SH-PadSH@2)") (class "Default")
      (node (ref "SD") (pin "SH@2") (pinfunction "SH_SH@2") (pintype "bidirectional"))
    )
    (net (code "71") (name "unconnected-(U$3-NRST-Pad7)") (class "Default")
      (node (ref "U$3") (pin "7") (pinfunction "NRST_7") (pintype "bidirectional"))
    )
    (net (code "72") (name "unconnected-(U$3-PA0-WKUP-Pad10)") (class "Default")
      (node (ref "U$3") (pin "10") (pinfunction "PA0-WKUP_10") (pintype "bidirectional"))
    )
    (net (code "73") (name "unconnected-(U$3-PA11-Pad32)") (class "Default")
      (node (ref "U$3") (pin "32") (pinfunction "PA11_32") (pintype "bidirectional"))
    )
    (net (code "74") (name "unconnected-(U$3-PA12-Pad33)") (class "Default")
      (node (ref "U$3") (pin "33") (pinfunction "PA12_33") (pintype "bidirectional"))
    )
    (net (code "75") (name "unconnected-(U$3-PA13-Pad34)") (class "Default")
      (node (ref "U$3") (pin "34") (pinfunction "PA13_34") (pintype "bidirectional"))
    )
    (net (code "76") (name "unconnected-(U$3-PB0-Pad18)") (class "Default")
      (node (ref "U$3") (pin "18") (pinfunction "PB0_18") (pintype "bidirectional"))
    )
    (net (code "77") (name "unconnected-(U$3-PB1-Pad19)") (class "Default")
      (node (ref "U$3") (pin "19") (pinfunction "PB1_19") (pintype "bidirectional"))
    )
    (net (code "78") (name "unconnected-(U$3-PB5-Pad41)") (class "Default")
      (node (ref "U$3") (pin "41") (pinfunction "PB5_41") (pintype "bidirectional"))
    )
    (net (code "79") (name "unconnected-(U$3-PB9-Pad46)") (class "Default")
      (node (ref "U$3") (pin "46") (pinfunction "PB9_46") (pintype "bidirectional"))
    )
    (net (code "80") (name "unconnected-(U$3-PC13-TAMPER-RTC-Pad2)") (class "Default")
      (node (ref "U$3") (pin "2") (pinfunction "PC13-TAMPER-RTC_2") (pintype "bidirectional"))
    )
    (net (code "81") (name "unconnected-(U$3-PC14_OSC32_IN-Pad3)") (class "Default")
      (node (ref "U$3") (pin "3") (pinfunction "PC14_OSC32_IN_3") (pintype "bidirectional"))
    )
    (net (code "82") (name "unconnected-(U$3-PC15_OSC32_OUT-Pad4)") (class "Default")
      (node (ref "U$3") (pin "4") (pinfunction "PC15_OSC32_OUT_4") (pintype "bidirectional"))
    )
    (net (code "83") (name "unconnected-(U$3-VBAT-Pad1)") (class "Default")
      (node (ref "U$3") (pin "1") (pinfunction "VBAT_1") (pintype "bidirectional"))
    )
    (net (code "84") (name "unconnected-(XBEE-AD0{slash}DIO0-Pad20)") (class "Default")
      (node (ref "XBEE") (pin "20") (pinfunction "AD0/DIO0_20") (pintype "bidirectional"))
    )
    (net (code "85") (name "unconnected-(XBEE-AD1{slash}DIO1-Pad19)") (class "Default")
      (node (ref "XBEE") (pin "19") (pinfunction "AD1/DIO1_19") (pintype "bidirectional"))
    )
    (net (code "86") (name "unconnected-(XBEE-AD2{slash}DIO2-Pad18)") (class "Default")
      (node (ref "XBEE") (pin "18") (pinfunction "AD2/DIO2_18") (pintype "bidirectional"))
    )
    (net (code "87") (name "unconnected-(XBEE-AD3{slash}DIO3-Pad17)") (class "Default")
      (node (ref "XBEE") (pin "17") (pinfunction "AD3/DIO3_17") (pintype "bidirectional"))
    )
    (net (code "88") (name "unconnected-(XBEE-AD4{slash}DIO4-Pad11)") (class "Default")
      (node (ref "XBEE") (pin "11") (pinfunction "AD4/DIO4_11") (pintype "bidirectional"))
    )
    (net (code "89") (name "unconnected-(XBEE-ASC{slash}AD5{slash}DIO5-Pad15)") (class "Default")
      (node (ref "XBEE") (pin "15") (pinfunction "ASC/AD5/DIO5_15") (pintype "bidirectional"))
    )
    (net (code "90") (name "unconnected-(XBEE-DO8-Pad4)") (class "Default")
      (node (ref "XBEE") (pin "4") (pinfunction "DO8_4") (pintype "output"))
    )
    (net (code "91") (name "unconnected-(XBEE-DTR{slash}DI8-Pad9)") (class "Default")
      (node (ref "XBEE") (pin "9") (pinfunction "DTR/DI8_9") (pintype "input"))
    )
    (net (code "92") (name "unconnected-(XBEE-ON{slash}SLEEP-Pad13)") (class "Default")
      (node (ref "XBEE") (pin "13") (pinfunction "ON/SLEEP_13") (pintype "output"))
    )
    (net (code "93") (name "unconnected-(XBEE-PWM0{slash}RSSI-Pad6)") (class "Default")
      (node (ref "XBEE") (pin "6") (pinfunction "PWM0/RSSI_6") (pintype "output"))
    )
    (net (code "94") (name "unconnected-(XBEE-PWM1-Pad7)") (class "Default")
      (node (ref "XBEE") (pin "7") (pinfunction "PWM1_7") (pintype "output"))
    )
    (net (code "95") (name "unconnected-(XBEE-RESERVED-Pad8)") (class "Default")
      (node (ref "XBEE") (pin "8") (pinfunction "RESERVED_8") (pintype "no_connect"))
    )
    (net (code "96") (name "unconnected-(XBEE-RESET-Pad5)") (class "Default")
      (node (ref "XBEE") (pin "5") (pinfunction "RESET_5") (pintype "input"))
    )
    (net (code "97") (name "unconnected-(XBEE-VREF-Pad14)") (class "Default")
      (node (ref "XBEE") (pin "14") (pinfunction "VREF_14") (pintype "input"))
    )
  )
)
